# Sheet1.net
KiCad netlist of a schematic drawn in Altium Designer
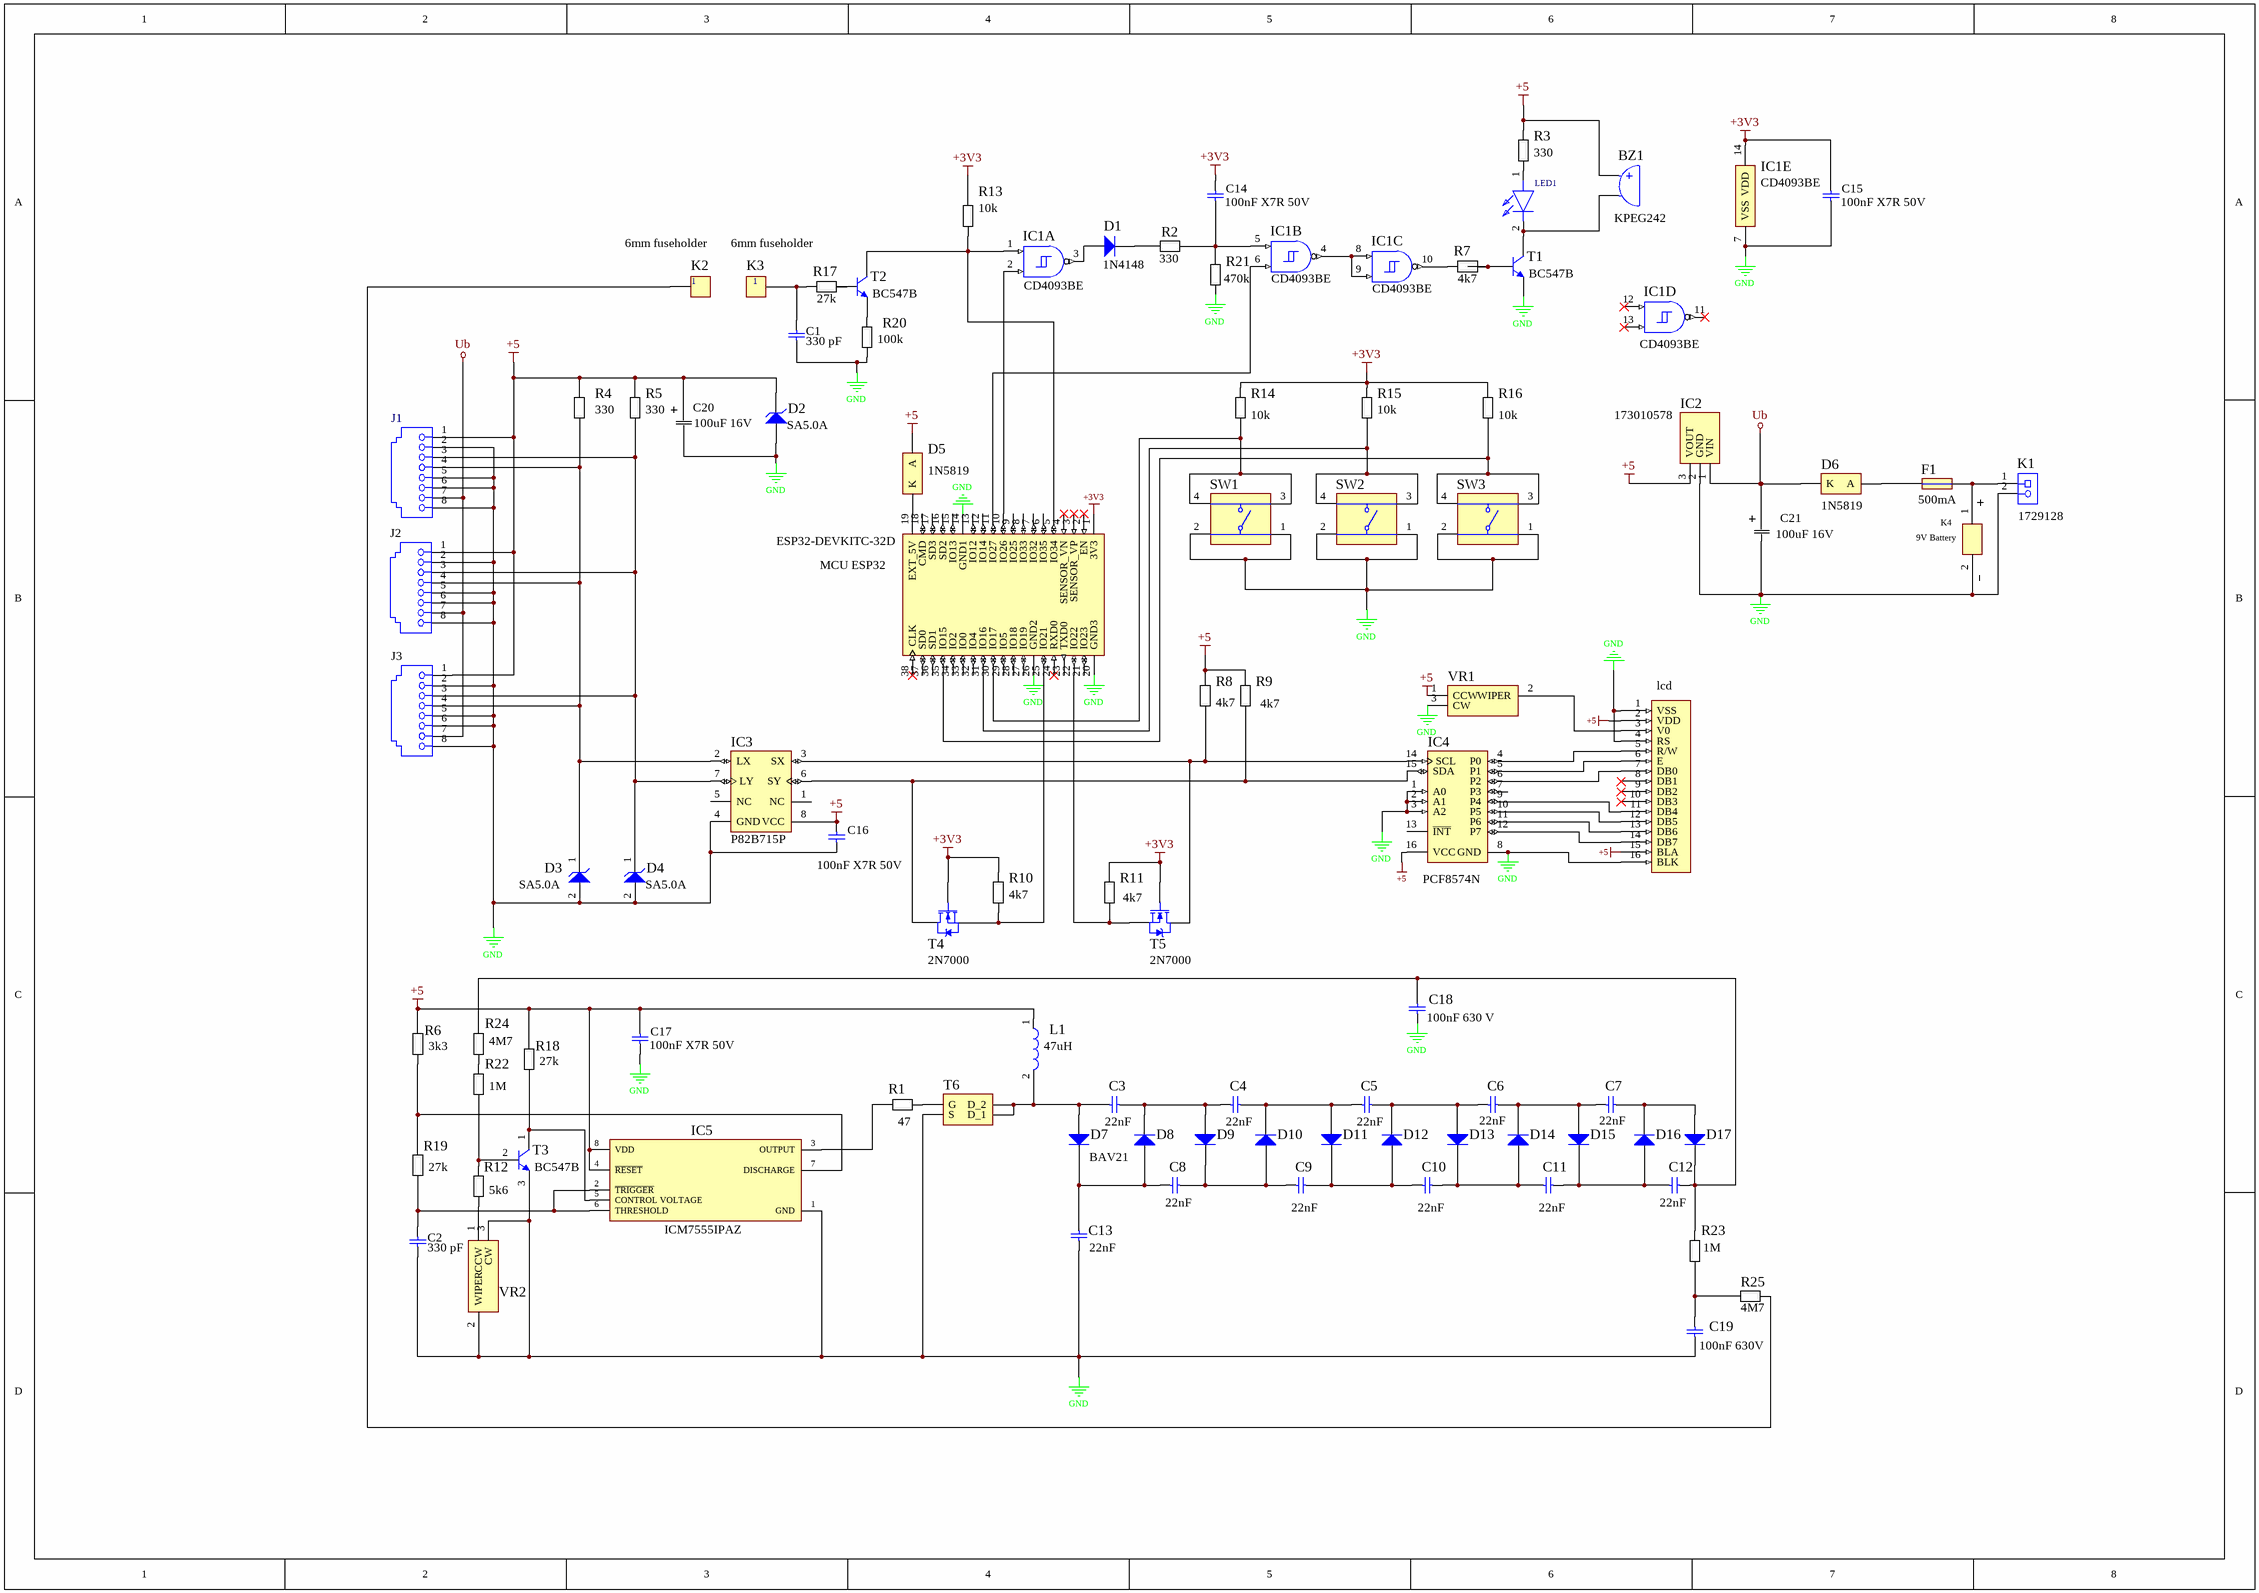
[diagram p0: Sheet1.SchDoc]

(export (version "E")
  (design (tool "Eeschema 10.0.6"))
  (components
    (comp (ref "BZ1")
      (value "KPEG242")
      (footprint "KINGS-KPEG242-2")
      (description "Piezo Indicator, 4100 Hz, 3 to 16 V, -20 to 70 degC, 2-Pin THD, RoHS")
      (fields (field (name "PARTNUMBER") "KPE-242") (field (name "MANUFACTURER") "KingstateElectronicsCorp."))
      (libsource (lib "Altium Content Vault") (part "KINGS-KPEG242-2"))
    )
    (comp (ref "C1")
      (value "330 pF")
      (footprint "CAPC2013X70X45NL10T25")
      (fields (field (name "MANUFACTURER") "Murata") (field (name "PART NUMBER") "GRM2165C1H332JA01D"))
      (libsource (lib "Altium Content Vault") (part "CAP"))
    )
    (comp (ref "C2")
      (value "330 pF")
      (footprint "CAPC2013X70X45NL10T25")
      (fields (field (name "MANUFACTURER") "Murata") (field (name "PART NUMBER") "GRM2165C1H332JA01D"))
      (libsource (lib "Altium Content Vault") (part "CAP"))
    )
    (comp (ref "C3")
      (value "22nF")
      (footprint "VISH-BFC233820104-2_V")
      (fields (field (name "PARTNUMBER") "BFC233820104") (field (name "MANUFACTURER") "Vishay Semiconductor"))
      (libsource (lib "Altium Content Vault") (part "VISH-CAP-NP-2"))
    )
    (comp (ref "C4")
      (value "22nF")
      (footprint "VISH-BFC233820104-2_V")
      (fields (field (name "PARTNUMBER") "BFC233820104") (field (name "MANUFACTURER") "Vishay Semiconductor"))
      (libsource (lib "Altium Content Vault") (part "VISH-CAP-NP-2"))
    )
    (comp (ref "C5")
      (value "22nF")
      (footprint "VISH-BFC233820104-2_V")
      (fields (field (name "PARTNUMBER") "BFC233820104") (field (name "MANUFACTURER") "Vishay Semiconductor"))
      (libsource (lib "Altium Content Vault") (part "VISH-CAP-NP-2"))
    )
    (comp (ref "C6")
      (value "22nF")
      (footprint "VISH-BFC233820104-2_V")
      (fields (field (name "PARTNUMBER") "BFC233820104") (field (name "MANUFACTURER") "Vishay Semiconductor"))
      (libsource (lib "Altium Content Vault") (part "VISH-CAP-NP-2"))
    )
    (comp (ref "C7")
      (value "22nF")
      (footprint "VISH-BFC233820104-2_V")
      (fields (field (name "PARTNUMBER") "BFC233820104") (field (name "MANUFACTURER") "Vishay Semiconductor"))
      (libsource (lib "Altium Content Vault") (part "VISH-CAP-NP-2"))
    )
    (comp (ref "C8")
      (value "22nF")
      (footprint "VISH-BFC233820104-2_V")
      (fields (field (name "PARTNUMBER") "BFC233820104") (field (name "MANUFACTURER") "Vishay Semiconductor"))
      (libsource (lib "Altium Content Vault") (part "VISH-CAP-NP-2"))
    )
    (comp (ref "C9")
      (value "22nF")
      (footprint "VISH-BFC233820104-2_V")
      (fields (field (name "PARTNUMBER") "BFC233820104") (field (name "MANUFACTURER") "Vishay Semiconductor"))
      (libsource (lib "Altium Content Vault") (part "VISH-CAP-NP-2"))
    )
    (comp (ref "C10")
      (value "22nF")
      (footprint "VISH-BFC233820104-2_V")
      (fields (field (name "PARTNUMBER") "BFC233820104") (field (name "MANUFACTURER") "Vishay Semiconductor"))
      (libsource (lib "Altium Content Vault") (part "VISH-CAP-NP-2"))
    )
    (comp (ref "C11")
      (value "22nF")
      (footprint "VISH-BFC233820104-2_V")
      (fields (field (name "PARTNUMBER") "BFC233820104") (field (name "MANUFACTURER") "Vishay Semiconductor"))
      (libsource (lib "Altium Content Vault") (part "VISH-CAP-NP-2"))
    )
    (comp (ref "C12")
      (value "22nF")
      (footprint "VISH-BFC233820104-2_V")
      (fields (field (name "PARTNUMBER") "BFC233820104") (field (name "MANUFACTURER") "Vishay Semiconductor"))
      (libsource (lib "Altium Content Vault") (part "VISH-CAP-NP-2"))
    )
    (comp (ref "C13")
      (value "22nF")
      (footprint "VISH-BFC233820104-2_V")
      (fields (field (name "PARTNUMBER") "BFC233820104") (field (name "MANUFACTURER") "Vishay Semiconductor"))
      (libsource (lib "Altium Content Vault") (part "VISH-CAP-NP-2"))
    )
    (comp (ref "C14")
      (value "100nF X7R 50V")
      (footprint "CAPC2013X70X45NL10T25")
      (fields (field (name "MANUFACTURER") "Murata") (field (name "PART NUMBER") "GRM2165C1H332JA01D"))
      (libsource (lib "Altium Content Vault") (part "CAP"))
    )
    (comp (ref "C15")
      (value "100nF X7R 50V")
      (footprint "CAPC2013X70X45NL10T25")
      (fields (field (name "MANUFACTURER") "Murata") (field (name "PART NUMBER") "GRM2165C1H332JA01D"))
      (libsource (lib "Altium Content Vault") (part "CAP"))
    )
    (comp (ref "C16")
      (value "100nF X7R 50V")
      (footprint "CAPC2013X70X45NL10T25")
      (fields (field (name "MANUFACTURER") "Murata") (field (name "PART NUMBER") "GRM2165C1H332JA01D"))
      (libsource (lib "Altium Content Vault") (part "CAP"))
    )
    (comp (ref "C17")
      (value "100nF X7R 50V")
      (footprint "CAPC2013X70X45NL10T25")
      (fields (field (name "MANUFACTURER") "Murata") (field (name "PART NUMBER") "GRM2165C1H332JA01D"))
      (libsource (lib "Altium Content Vault") (part "CAP"))
    )
    (comp (ref "C18")
      (value "100nF 630 V")
      (footprint "CAPC1812(4532)125_M")
      (description "CAP 470nF 50V ±10% 1812 (4532 Metric) Thickness 1.25mm SMD")
      (fields (field (name "TOLERANCE") "Â±10%"))
      (libsource (lib "Altium Content Vault") (part "CAP"))
    )
    (comp (ref "C19")
      (value "100nF 630V")
      (footprint "CAPC1812(4532)125_M")
      (description "CAP 470nF 50V ±10% 1812 (4532 Metric) Thickness 1.25mm SMD")
      (fields (field (name "TOLERANCE") "Â±10%"))
      (libsource (lib "Altium Content Vault") (part "CAP"))
    )
    (comp (ref "C20")
      (value "100uF 16V")
      (footprint "100uf 16V elco")
      (libsource (lib "Schlib2") (part "Component_1"))
    )
    (comp (ref "C21")
      (value "100uF 16V")
      (footprint "100uf 16V elco")
      (libsource (lib "Schlib2") (part "Component_1"))
    )
    (comp (ref "D1")
      (value "1N4148")
      (footprint "NXP-SOD27-2_V")
      (description "High-speed Diode, 100 V, 450 mA, 2-Pin SOD27, RoHS")
      (fields (field (name "MANUFACTURER") "NXP Semiconductors"))
      (libsource (lib "Altium Content Vault") (part "NXP-A1K2-2"))
    )
    (comp (ref "D2")
      (value "SA5.0A")
      (footprint "ONSC-AXIAL_LEAD-2-59AA-01_P")
      (fields (field (name "MANUFACTURER") "On Semiconductor"))
      (libsource (lib "") (part "ONSC-K1A2-2_1"))
    )
    (comp (ref "D3")
      (value "SA5.0A")
      (footprint "ONSC-AXIAL_LEAD-2-59AA-01_P")
      (fields (field (name "MANUFACTURER") "On Semiconductor"))
      (libsource (lib "Altium Content Vault") (part "ONSC-K1A2-2"))
    )
    (comp (ref "D4")
      (value "SA5.0A")
      (footprint "ONSC-AXIAL_LEAD-2-59AA-01_P")
      (fields (field (name "MANUFACTURER") "On Semiconductor"))
      (libsource (lib "Altium Content Vault") (part "ONSC-K1A2-2"))
    )
    (comp (ref "D5")
      (value "1N5819")
      (footprint "ONSC-AXIAL_LEAD-2-59-10_P")
      (description "Rectifier, 2-Pin Axial_Lead, Pb-Free, Bulk Bag")
      (fields (field (name "MANUFACTURER") "On Semiconductor"))
      (libsource (lib "") (part "ONSC-D-K1A2-2_A_1"))
    )
    (comp (ref "D6")
      (value "1N5819")
      (footprint "ONSC-AXIAL_LEAD-2-59-10_P")
      (description "Rectifier, 2-Pin Axial_Lead, Pb-Free, Bulk Bag")
      (fields (field (name "MANUFACTURER") "On Semiconductor"))
      (libsource (lib "Altium Content Vault") (part "ONSC-D-K1A2-2_A"))
    )
    (comp (ref "D7")
      (value "BAV21")
      (footprint "MCSM-DO-35-2")
      (description "BAV21TR Diode 250V 0.2A DO35")
      (fields (field (name "PARTNUMBER") "1N4148-1") (field (name "MANUFACTURER") "Microsemi"))
      (libsource (lib "Altium Content Vault") (part "D-AK-2"))
    )
    (comp (ref "D8")
      (value "BAV21")
      (footprint "MCSM-DO-35-2")
      (description "BAV21TR Diode 250V 0.2A DO35")
      (fields (field (name "PARTNUMBER") "1N4148-1") (field (name "MANUFACTURER") "Microsemi"))
      (libsource (lib "Altium Content Vault") (part "D-AK-2"))
    )
    (comp (ref "D9")
      (value "BAV21")
      (footprint "MCSM-DO-35-2")
      (description "BAV21TR Diode 250V 0.2A DO35")
      (fields (field (name "PARTNUMBER") "1N4148-1") (field (name "MANUFACTURER") "Microsemi"))
      (libsource (lib "Altium Content Vault") (part "D-AK-2"))
    )
    (comp (ref "D10")
      (value "BAV21")
      (footprint "MCSM-DO-35-2")
      (description "BAV21TR Diode 250V 0.2A DO35")
      (fields (field (name "PARTNUMBER") "1N4148-1") (field (name "MANUFACTURER") "Microsemi"))
      (libsource (lib "Altium Content Vault") (part "D-AK-2"))
    )
    (comp (ref "D11")
      (value "BAV21")
      (footprint "MCSM-DO-35-2")
      (description "BAV21TR Diode 250V 0.2A DO35")
      (fields (field (name "PARTNUMBER") "1N4148-1") (field (name "MANUFACTURER") "Microsemi"))
      (libsource (lib "Altium Content Vault") (part "D-AK-2"))
    )
    (comp (ref "D12")
      (value "BAV21")
      (footprint "MCSM-DO-35-2")
      (description "BAV21TR Diode 250V 0.2A DO35")
      (fields (field (name "PARTNUMBER") "1N4148-1") (field (name "MANUFACTURER") "Microsemi"))
      (libsource (lib "Altium Content Vault") (part "D-AK-2"))
    )
    (comp (ref "D13")
      (value "BAV21")
      (footprint "MCSM-DO-35-2")
      (description "BAV21TR Diode 250V 0.2A DO35")
      (fields (field (name "PARTNUMBER") "1N4148-1") (field (name "MANUFACTURER") "Microsemi"))
      (libsource (lib "Altium Content Vault") (part "D-AK-2"))
    )
    (comp (ref "D14")
      (value "BAV21")
      (footprint "MCSM-DO-35-2")
      (description "BAV21TR Diode 250V 0.2A DO35")
      (fields (field (name "PARTNUMBER") "1N4148-1") (field (name "MANUFACTURER") "Microsemi"))
      (libsource (lib "Altium Content Vault") (part "D-AK-2"))
    )
    (comp (ref "D15")
      (value "BAV21")
      (footprint "MCSM-DO-35-2")
      (description "BAV21TR Diode 250V 0.2A DO35")
      (fields (field (name "PARTNUMBER") "1N4148-1") (field (name "MANUFACTURER") "Microsemi"))
      (libsource (lib "Altium Content Vault") (part "D-AK-2"))
    )
    (comp (ref "D16")
      (value "BAV21")
      (footprint "MCSM-DO-35-2")
      (description "BAV21TR Diode 250V 0.2A DO35")
      (fields (field (name "PARTNUMBER") "1N4148-1") (field (name "MANUFACTURER") "Microsemi"))
      (libsource (lib "Altium Content Vault") (part "D-AK-2"))
    )
    (comp (ref "D17")
      (value "BAV21")
      (footprint "MCSM-DO-35-2")
      (description "BAV21TR Diode 250V 0.2A DO35")
      (fields (field (name "PARTNUMBER") "1N4148-1") (field (name "MANUFACTURER") "Microsemi"))
      (libsource (lib "Altium Content Vault") (part "D-AK-2"))
    )
    (comp (ref "F1")
      (value "500mA")
      (footprint "39211000000")
      (description "Fuse")
      (fields
        (field (name "MANUFACTURER_PART_NUMBER") "39211000000")
        (field (name "MOUSER PART NUMBER") "576-3921100000")
      )
      (libsource (lib "SamacSys") (part "39211000000"))
    )
    (comp (ref "IC1")
      (value "CD4093BE")
      (footprint "N0014A")
      (description "CMOS Quad 2-Input NAND Schmitt Triggers, N0014A, TUBE")
      (fields
        (field (name "MANUFACTURER") "Texas Instruments")
        (field (name "GENERIC PART NUMBER") "CD4093B")
      )
      (libsource (lib "Altium Content Vault") (part "TI-NAND-4-2IN-14_A-SCHMITT"))
    )
    (comp (ref "IC2")
      (value "173010578")
      (footprint "173010578")
      (description "Undefined or Miscellaneous")
      (fields (field (name "MOUSER2 PART NUMBER") "710-173010578"))
      (libsource (lib "SamacSys") (part "173010578"))
    )
    (comp (ref "IC3")
      (value "P82B715P")
      (footprint "P0008A")
      (description "I2C Bus Extender, 2 Channel Width, 3.0 to 12.0 V, -40 to 85 degC, 8-pin PDIP (P), Pb-Free (RoHS)")
      (fields (field (name "MANUFACTURER") "Texas Instruments"))
      (libsource (lib "Altium Content Vault") (part "TI-P82B715-PDIP_P-8"))
    )
    (comp (ref "IC4")
      (value "PCF8574N")
      (footprint "N0016A")
      (description "Remote 8-Bit I/O Expander for I2C-Bus, 2.5 to 6 V, -40 to 85 degC, 16-pin PDIP (N), Pb-Free (RoHS)")
      (fields (field (name "MANUFACTURER") "Texas Instruments"))
      (libsource (lib "Altium Content Vault") (part "TI-PCF8574-PDIP_N-16"))
    )
    (comp (ref "IC5")
      (value "ICM7555IPAZ")
      (footprint "Intersil_ICM7555IPAZ_0")
      (libsource (lib "IC_Intersil_ICM7555IPAZ_eec") (part "ICM7555IPAZ"))
    )
    (comp (ref "J1")
      (value "615008138021")
      (footprint "615008138021")
      (description "Modular Jack WR-MJ, Plastic, Vertical Entry, THT, 8P8C")
      (fields (field (name "MANUFACTURER") "Wurth Elektronik") (field (name "PUBLISHER") "WurthElektronik"))
      (libsource (lib "Altium Content Vault") (part "WE-CN-1P-F-J8"))
    )
    (comp (ref "J2")
      (value "615008138021")
      (footprint "615008138021")
      (description "Modular Jack WR-MJ, Plastic, Vertical Entry, THT, 8P8C")
      (fields (field (name "MANUFACTURER") "Wurth Elektronik") (field (name "PUBLISHER") "WurthElektronik"))
      (libsource (lib "Altium Content Vault") (part "WE-CN-1P-F-J8"))
    )
    (comp (ref "J3")
      (value "615008138021")
      (footprint "615008138021")
      (description "Modular Jack WR-MJ, Plastic, Vertical Entry, THT, 8P8C")
      (fields (field (name "MANUFACTURER") "Wurth Elektronik") (field (name "PUBLISHER") "WurthElektronik"))
      (libsource (lib "Altium Content Vault") (part "WE-CN-1P-F-J8"))
    )
    (comp (ref "K1")
      (value "1729128")
      (footprint "PHOE-1729128-2_V")
      (description "PCB Terminal Block, 13.5 A, 400 V, 2-Pin THD, RoHS, Bulk")
      (fields (field (name "MANUFACTURER") "Phoenix Contact"))
      (libsource (lib "Altium Content Vault") (part "CN-2P-F-R2"))
    )
    (comp (ref "K2")
      (value "6mm fuseholder")
      (footprint "FP-102-MFG")
      (description "FUSE CLIP CARTRIDGE 250V 15A PCB")
      (fields
        (field (name "MANUFACTURER") "Littelfuse Inc")
        (field (name "OCTOPART") "https://octopart.com/01020071z-littelfuse-18837869")
      )
      (libsource (lib "") (part "600373309f0643ccfefc365bd0e8f7b_1"))
    )
    (comp (ref "K3")
      (value "6mm fuseholder")
      (footprint "FP-102-MFG")
      (description "FUSE CLIP CARTRIDGE 250V 15A PCB")
      (fields
        (field (name "MANUFACTURER") "Littelfuse Inc")
        (field (name "OCTOPART") "https://octopart.com/01020071z-littelfuse-18837869")
      )
      (libsource (lib "Altium Content Vault") (part "600373309f0643ccfefc365bd0e8f7b"))
    )
    (comp (ref "K4")
      (value "9V Battery")
      (footprint "PCBComponent_1")
      (libsource (lib "Schlib3") (part "Component_1"))
    )
    (comp (ref "L1")
      (value "47uH")
      (footprint "WE-TI-LS")
      (description "Radial Leaded Wire Wound Inductor WE-TI, L = 100 µH")
      (libsource (lib "Altium Content Vault") (part "PAS-IND-INDUCTOR-2"))
    )
    (comp (ref "lcd") (value "~") (footprint "PCBComponent_1") (libsource (lib "1602a") (part "Component_1")))
    (comp (ref "LED1")
      (value "151033GS03000")
      (footprint "SamacSys:151033GS03000")
      (description "LED")
      (fields (field (name "MOUSER PART NUMBER") "710-151033GS03000"))
      (libsource (lib "SamacSys") (part "151033GS03000"))
    )
    (comp (ref "MCU ESP32")
      (value "ESP32-DEVKITC-32D")
      (footprint "MODULE_ESP32-DEVKITC-32D")
      (description "EVAL BOARD FOR ESP-WROOM-32")
      (fields (field (name "MF") "Espressif Systems"))
      (libsource (lib "ESP32-DEVKITC-32D") (part "ESP32-DEVKITC-32D"))
    )
    (comp (ref "R1")
      (value "47")
      (footprint "FP-RC1206-IPC_C")
      (libsource (lib "") (part "1206 weerstand_2"))
    )
    (comp (ref "R2")
      (value "330")
      (footprint "FP-RC1206-IPC_C")
      (libsource (lib "") (part "1206 weerstand_3"))
    )
    (comp (ref "R3")
      (value "330")
      (footprint "FP-RC1206-IPC_C")
      (libsource (lib "") (part "1206 weerstand_1"))
    )
    (comp (ref "R4")
      (value "330")
      (footprint "FP-RC1206-IPC_C")
      (libsource (lib "Schlib1") (part "1206 weerstand"))
    )
    (comp (ref "R5")
      (value "330")
      (footprint "FP-RC1206-IPC_C")
      (libsource (lib "Schlib1") (part "1206 weerstand"))
    )
    (comp (ref "R6")
      (value "3k3")
      (footprint "FP-RC1206-IPC_C")
      (libsource (lib "Schlib1") (part "1206 weerstand"))
    )
    (comp (ref "R7")
      (value "4k7")
      (footprint "FP-RC1206-IPC_C")
      (libsource (lib "") (part "1206 weerstand_2"))
    )
    (comp (ref "R8")
      (value "4k7")
      (footprint "FP-RC1206-IPC_C")
      (libsource (lib "Schlib1") (part "1206 weerstand"))
    )
    (comp (ref "R9")
      (value "4k7")
      (footprint "FP-RC1206-IPC_C")
      (libsource (lib "Schlib1") (part "1206 weerstand"))
    )
    (comp (ref "R10")
      (value "4k7")
      (footprint "FP-RC1206-IPC_C")
      (libsource (lib "Schlib1") (part "1206 weerstand"))
    )
    (comp (ref "R11")
      (value "4k7")
      (footprint "FP-RC1206-IPC_C")
      (libsource (lib "") (part "1206 weerstand_3"))
    )
    (comp (ref "R12")
      (value "5k6")
      (footprint "FP-RC1206-IPC_C")
      (libsource (lib "Schlib1") (part "1206 weerstand"))
    )
    (comp (ref "R13")
      (value "10k")
      (footprint "FP-RC1206-IPC_C")
      (libsource (lib "") (part "1206 weerstand_1"))
    )
    (comp (ref "R14")
      (value "10k")
      (footprint "FP-RC1206-IPC_C")
      (libsource (lib "Schlib1") (part "1206 weerstand"))
    )
    (comp (ref "R15")
      (value "10k")
      (footprint "FP-RC1206-IPC_C")
      (libsource (lib "Schlib1") (part "1206 weerstand"))
    )
    (comp (ref "R16")
      (value "10k")
      (footprint "FP-RC1206-IPC_C")
      (libsource (lib "Schlib1") (part "1206 weerstand"))
    )
    (comp (ref "R17")
      (value "27k")
      (footprint "FP-RC1206-IPC_C")
      (libsource (lib "") (part "1206 weerstand_2"))
    )
    (comp (ref "R18")
      (value "27k")
      (footprint "FP-RC1206-IPC_C")
      (libsource (lib "Schlib1") (part "1206 weerstand"))
    )
    (comp (ref "R19")
      (value "27k")
      (footprint "FP-RC1206-IPC_C")
      (libsource (lib "Schlib1") (part "1206 weerstand"))
    )
    (comp (ref "R20")
      (value "100k")
      (footprint "FP-RC1206-IPC_C")
      (libsource (lib "") (part "1206 weerstand_1"))
    )
    (comp (ref "R21")
      (value "470k")
      (footprint "FP-RC1206-IPC_C")
      (libsource (lib "Schlib1") (part "1206 weerstand"))
    )
    (comp (ref "R22")
      (value "1M")
      (footprint "RES_VR25")
      (description "No Description Available")
      (fields
        (field (name "MANUFACTURER_PART_NUMBER") "VR25000001004JA100")
        (field (name "COPYRIGHT") "Copyright (C) 2018 Accelerated Designs. All rights reserved")
      )
      (libsource (lib "2021-03-05_17-49-49") (part "VR25000001004JA100"))
    )
    (comp (ref "R23")
      (value "1M")
      (footprint "RES_VR25")
      (description "No Description Available")
      (fields
        (field (name "MANUFACTURER_PART_NUMBER") "VR25000001004JA100")
        (field (name "COPYRIGHT") "Copyright (C) 2018 Accelerated Designs. All rights reserved")
      )
      (libsource (lib "2021-03-05_17-49-49") (part "VR25000001004JA100"))
    )
    (comp (ref "R24")
      (value "4M7")
      (footprint "RES_VR25")
      (description "No Description Available")
      (fields
        (field (name "MANUFACTURER_PART_NUMBER") "VR25000001004JA100")
        (field (name "COPYRIGHT") "Copyright (C) 2018 Accelerated Designs. All rights reserved")
      )
      (libsource (lib "2021-03-05_17-49-49") (part "VR25000001004JA100"))
    )
    (comp (ref "R25")
      (value "4M7")
      (footprint "RES_VR25")
      (description "No Description Available")
      (fields
        (field (name "MANUFACTURER_PART_NUMBER") "VR25000001004JA100")
        (field (name "COPYRIGHT") "Copyright (C) 2018 Accelerated Designs. All rights reserved")
      )
      (libsource (lib "") (part "VR25000001004JA100_1"))
    )
    (comp (ref "SW1")
      (value "tactile switch 10mm")
      (footprint "TECO-1825910-6_V")
      (description "Tact Switch, SPST-NO, 0.05 A, -35 to 85 degC, 4-Pin THD, RoHS, Bulk")
      (fields (field (name "PART NO") "1825910-6") (field (name "MANUFACTURER") "TE Connectivity"))
      (libsource (lib "Altium Content Vault") (part "SW-SPST-4_A"))
    )
    (comp (ref "SW2")
      (value "tactile switch 10mm")
      (footprint "TECO-1825910-6_V")
      (description "Tact Switch, SPST-NO, 0.05 A, -35 to 85 degC, 4-Pin THD, RoHS, Bulk")
      (fields (field (name "PART NO") "1825910-6") (field (name "MANUFACTURER") "TE Connectivity"))
      (libsource (lib "Altium Content Vault") (part "SW-SPST-4_A"))
    )
    (comp (ref "SW3")
      (value "tactile switch 10mm")
      (footprint "TECO-1825910-6_V")
      (description "Tact Switch, SPST-NO, 0.05 A, -35 to 85 degC, 4-Pin THD, RoHS, Bulk")
      (fields (field (name "PART NO") "1825910-6") (field (name "MANUFACTURER") "TE Connectivity"))
      (libsource (lib "Altium Content Vault") (part "SW-SPST-4_A"))
    )
    (comp (ref "T1")
      (value "BC547B")
      (footprint "ONSC-TO-92-3-29-11")
      (description "Amplifier Transistor, NPN Silicon, 3-Pin TO-92, Bulk Box")
      (fields (field (name "MANUFACTURER") "On Semiconductor"))
      (libsource (lib "") (part "ONSC-NPN-C1B2E3-3_1"))
    )
    (comp (ref "T2")
      (value "BC547B")
      (footprint "ONSC-TO-92-3-29-11")
      (description "Amplifier Transistor, NPN Silicon, 3-Pin TO-92, Bulk Box")
      (fields (field (name "MANUFACTURER") "On Semiconductor"))
      (libsource (lib "") (part "ONSC-NPN-C1B2E3-3_1"))
    )
    (comp (ref "T3")
      (value "BC547B")
      (footprint "ONSC-TO-92-3-29-11")
      (description "Amplifier Transistor, NPN Silicon, 3-Pin TO-92, Bulk Box")
      (fields (field (name "MANUFACTURER") "On Semiconductor"))
      (libsource (lib "Altium Content Vault") (part "ONSC-NPN-C1B2E3-3"))
    )
    (comp (ref "T4")
      (value "2N7000")
      (footprint "ONSC-TO-92-3-29-11")
      (description "Small Signal MOSFET, 200 mA, 60 V, N-Channel, 3-Pin TO-92, Bulk Box")
      (fields (field (name "MANUFACTURER") "On Semiconductor"))
      (libsource (lib "Altium Content Vault") (part "ONSC-NMOS-S1G2D3-3"))
    )
    (comp (ref "T5")
      (value "2N7000")
      (footprint "ONSC-TO-92-3-29-11")
      (description "Small Signal MOSFET, 200 mA, 60 V, N-Channel, 3-Pin TO-92, Bulk Box")
      (fields (field (name "MANUFACTURER") "On Semiconductor"))
      (libsource (lib "Altium Content Vault") (part "ONSC-NMOS-S1G2D3-3"))
    )
    (comp (ref "T6")
      (value "~")
      (footprint "SamacSys:DIP920W60P254L490H337Q4N")
      (description "MOSFET (N-Channel)")
      (fields
        (field (name "MANUFACTURER_PART_NUMBER") "IRLD110PBF")
        (field (name "MOUSER PART NUMBER") "844-IRLD110PBF")
      )
      (libsource (lib "SamacSys") (part "IRLD110PBF"))
    )
    (comp (ref "VR1")
      (value "~")
      (footprint "RM065102")
      (description "Variable Resistor")
      (fields (field (name "MANUFACTURER_PART_NUMBER") "RM-065-102"))
      (libsource (lib "SamacSys") (part "RM-065-102"))
    )
    (comp (ref "VR2")
      (value "~")
      (footprint "RM065102")
      (description "Variable Resistor")
      (fields (field (name "MANUFACTURER_PART_NUMBER") "RM-065-102"))
      (libsource (lib "") (part "RM-065-102_1"))
    )
  )
  (nets
    (net (code "1") (name "+3V3") (class "Default")
      (node (ref "C14") (pin "2") (pinfunction "2_2") (pintype "passive"))
      (node (ref "C15") (pin "2") (pinfunction "2_2") (pintype "passive"))
      (node (ref "IC1") (pin "14") (pinfunction "VDD_14") (pintype "power_in"))
      (node (ref "MCU ESP32") (pin "1") (pinfunction "3V3_1") (pintype "power_in"))
      (node (ref "R10") (pin "2") (pintype "passive"))
      (node (ref "R11") (pin "2") (pintype "passive"))
      (node (ref "R13") (pin "1") (pintype "passive"))
      (node (ref "R14") (pin "2") (pintype "passive"))
      (node (ref "R15") (pin "2") (pintype "passive"))
      (node (ref "R16") (pin "2") (pintype "passive"))
      (node (ref "T4") (pin "2") (pinfunction "G_2") (pintype "passive"))
      (node (ref "T5") (pin "2") (pinfunction "G_2") (pintype "passive"))
    )
    (net (code "2") (name "+5") (class "Default")
      (node (ref "BZ1") (pin "1") (pinfunction "1_1") (pintype "passive"))
      (node (ref "C16") (pin "2") (pinfunction "2_2") (pintype "passive"))
      (node (ref "C17") (pin "2") (pinfunction "2_2") (pintype "passive"))
      (node (ref "C20") (pin "2") (pintype "passive"))
      (node (ref "D2") (pin "1") (pinfunction "K_1") (pintype "passive"))
      (node (ref "D5") (pin "2") (pinfunction "A_2") (pintype "passive"))
      (node (ref "IC2") (pin "3") (pinfunction "VOUT_3") (pintype "passive"))
      (node (ref "IC3") (pin "8") (pinfunction "VCC_8") (pintype "power_in"))
      (node (ref "IC4") (pin "16") (pinfunction "VCC_16") (pintype "power_in"))
      (node (ref "IC5") (pin "4") (pinfunction "~{RESET}_4") (pintype "passive"))
      (node (ref "IC5") (pin "8") (pinfunction "VDD_8") (pintype "passive"))
      (node (ref "J1") (pin "1") (pinfunction "1_1") (pintype "passive"))
      (node (ref "J2") (pin "1") (pinfunction "1_1") (pintype "passive"))
      (node (ref "J3") (pin "1") (pinfunction "1_1") (pintype "passive"))
      (node (ref "L1") (pin "1") (pinfunction "1_1") (pintype "passive"))
      (node (ref "R18") (pin "2") (pintype "passive"))
      (node (ref "R3") (pin "1") (pintype "passive"))
      (node (ref "R4") (pin "2") (pintype "passive"))
      (node (ref "R5") (pin "2") (pintype "passive"))
      (node (ref "R6") (pin "2") (pintype "passive"))
      (node (ref "R8") (pin "2") (pintype "passive"))
      (node (ref "R9") (pin "2") (pintype "passive"))
      (node (ref "VR1") (pin "1") (pinfunction "CCW_1") (pintype "passive"))
      (node (ref "lcd") (pin "15") (pinfunction "BLA_15") (pintype "input"))
      (node (ref "lcd") (pin "2") (pinfunction "VDD_2") (pintype "input"))
    )
    (net (code "3") (name "GND") (class "Default")
      (node (ref "C1") (pin "1") (pinfunction "1_1") (pintype "passive"))
      (node (ref "C13") (pin "1") (pinfunction "1_1") (pintype "passive"))
      (node (ref "C15") (pin "1") (pinfunction "1_1") (pintype "passive"))
      (node (ref "C16") (pin "1") (pinfunction "1_1") (pintype "passive"))
      (node (ref "C17") (pin "1") (pinfunction "1_1") (pintype "passive"))
      (node (ref "C18") (pin "1") (pinfunction "1_1") (pintype "passive"))
      (node (ref "C19") (pin "1") (pinfunction "1_1") (pintype "passive"))
      (node (ref "C2") (pin "1") (pinfunction "1_1") (pintype "passive"))
      (node (ref "C20") (pin "1") (pintype "passive"))
      (node (ref "C21") (pin "1") (pintype "passive"))
      (node (ref "D2") (pin "2") (pinfunction "A_2") (pintype "passive"))
      (node (ref "D3") (pin "2") (pinfunction "A_2") (pintype "passive"))
      (node (ref "D4") (pin "2") (pinfunction "A_2") (pintype "passive"))
      (node (ref "IC1") (pin "7") (pinfunction "VSS_7") (pintype "power_in"))
      (node (ref "IC2") (pin "2") (pinfunction "GND_2") (pintype "passive"))
      (node (ref "IC3") (pin "4") (pinfunction "GND_4") (pintype "power_in"))
      (node (ref "IC4") (pin "1") (pinfunction "A0_1") (pintype "input"))
      (node (ref "IC4") (pin "2") (pinfunction "A1_2") (pintype "input"))
      (node (ref "IC4") (pin "3") (pinfunction "A2_3") (pintype "input"))
      (node (ref "IC4") (pin "8") (pinfunction "GND_8") (pintype "power_in"))
      (node (ref "IC5") (pin "1") (pinfunction "GND_1") (pintype "passive"))
      (node (ref "J1") (pin "2") (pinfunction "2_2") (pintype "passive"))
      (node (ref "J1") (pin "5") (pinfunction "5_5") (pintype "passive"))
      (node (ref "J1") (pin "6") (pinfunction "6_6") (pintype "passive"))
      (node (ref "J1") (pin "8") (pinfunction "8_8") (pintype "passive"))
      (node (ref "J2") (pin "2") (pinfunction "2_2") (pintype "passive"))
      (node (ref "J2") (pin "5") (pinfunction "5_5") (pintype "passive"))
      (node (ref "J2") (pin "6") (pinfunction "6_6") (pintype "passive"))
      (node (ref "J2") (pin "8") (pinfunction "8_8") (pintype "passive"))
      (node (ref "J3") (pin "2") (pinfunction "2_2") (pintype "passive"))
      (node (ref "J3") (pin "5") (pinfunction "5_5") (pintype "passive"))
      (node (ref "J3") (pin "6") (pinfunction "6_6") (pintype "passive"))
      (node (ref "J3") (pin "8") (pinfunction "8_8") (pintype "passive"))
      (node (ref "K1") (pin "2") (pinfunction "2_2") (pintype "passive"))
      (node (ref "K4") (pin "2") (pintype "power_in"))
      (node (ref "MCU ESP32") (pin "14") (pinfunction "GND1_14") (pintype "power_in"))
      (node (ref "MCU ESP32") (pin "20") (pinfunction "GND3_20") (pintype "power_in"))
      (node (ref "MCU ESP32") (pin "26") (pinfunction "GND2_26") (pintype "power_in"))
      (node (ref "R20") (pin "2") (pintype "passive"))
      (node (ref "R21") (pin "1") (pintype "passive"))
      (node (ref "SW1") (pin "1") (pinfunction "1_1") (pintype "passive"))
      (node (ref "SW1") (pin "2") (pinfunction "2_2") (pintype "passive"))
      (node (ref "SW2") (pin "1") (pinfunction "1_1") (pintype "passive"))
      (node (ref "SW2") (pin "2") (pinfunction "2_2") (pintype "passive"))
      (node (ref "SW3") (pin "1") (pinfunction "1_1") (pintype "passive"))
      (node (ref "SW3") (pin "2") (pinfunction "2_2") (pintype "passive"))
      (node (ref "T1") (pin "3") (pinfunction "E_3") (pintype "passive"))
      (node (ref "T3") (pin "3") (pinfunction "E_3") (pintype "passive"))
      (node (ref "T6") (pin "2") (pinfunction "S_2") (pintype "passive"))
      (node (ref "VR1") (pin "3") (pinfunction "CW_3") (pintype "passive"))
      (node (ref "VR2") (pin "2") (pinfunction "WIPER_2") (pintype "passive"))
      (node (ref "VR2") (pin "3") (pinfunction "CW_3") (pintype "passive"))
      (node (ref "lcd") (pin "1") (pinfunction "VSS_1") (pintype "input"))
      (node (ref "lcd") (pin "16") (pinfunction "BLK_16") (pintype "input"))
      (node (ref "lcd") (pin "4") (pinfunction "RS_4") (pintype "input"))
    )
    (net (code "4") (name "Net-(C1-Pad2)") (class "Default")
      (node (ref "C1") (pin "2") (pinfunction "2_2") (pintype "passive"))
      (node (ref "K3") (pin "1") (pinfunction "1_1") (pintype "passive"))
      (node (ref "R17") (pin "2") (pintype "passive"))
    )
    (net (code "5") (name "Net-(C19-Pad2)") (class "Default")
      (node (ref "C19") (pin "2") (pinfunction "2_2") (pintype "passive"))
      (node (ref "R23") (pin "1") (pintype "passive"))
      (node (ref "R25") (pin "1") (pintype "passive"))
    )
    (net (code "6") (name "Net-(D1-A)") (class "Default")
      (node (ref "D1") (pin "1") (pinfunction "A_1") (pintype "passive"))
      (node (ref "IC1") (pin "3") (pinfunction "J_3") (pintype "output"))
    )
    (net (code "7") (name "Net-(D1-K)") (class "Default")
      (node (ref "D1") (pin "2") (pinfunction "K_2") (pintype "passive"))
      (node (ref "R2") (pin "1") (pintype "passive"))
    )
    (net (code "8") (name "Net-(D3-K)") (class "Default")
      (node (ref "D3") (pin "1") (pinfunction "K_1") (pintype "passive"))
      (node (ref "IC3") (pin "2") (pinfunction "LX_2") (pintype "bidirectional"))
      (node (ref "J1") (pin "4") (pinfunction "4_4") (pintype "passive"))
      (node (ref "J2") (pin "4") (pinfunction "4_4") (pintype "passive"))
      (node (ref "J3") (pin "4") (pinfunction "4_4") (pintype "passive"))
      (node (ref "R4") (pin "1") (pintype "passive"))
    )
    (net (code "9") (name "Net-(D4-K)") (class "Default")
      (node (ref "D4") (pin "1") (pinfunction "K_1") (pintype "passive"))
      (node (ref "IC3") (pin "7") (pinfunction "LY_7") (pintype "bidirectional"))
      (node (ref "J1") (pin "3") (pinfunction "3_3") (pintype "passive"))
      (node (ref "J2") (pin "3") (pinfunction "3_3") (pintype "passive"))
      (node (ref "J3") (pin "3") (pinfunction "3_3") (pintype "passive"))
      (node (ref "R5") (pin "1") (pintype "passive"))
    )
    (net (code "10") (name "Net-(D5-K)") (class "Default")
      (node (ref "D5") (pin "1") (pinfunction "K_1") (pintype "passive"))
      (node (ref "MCU ESP32") (pin "19") (pinfunction "EXT_5V_19") (pintype "power_in"))
    )
    (net (code "11") (name "Net-(D6-A)") (class "Default")
      (node (ref "D6") (pin "2") (pinfunction "A_2") (pintype "passive"))
      (node (ref "F1") (pin "1") (pinfunction "1_1") (pintype "passive"))
    )
    (net (code "12") (name "Net-(D7-A)") (class "Default")
      (node (ref "C3") (pin "1") (pinfunction "1_1") (pintype "passive"))
      (node (ref "D7") (pin "1") (pinfunction "A_1") (pintype "passive"))
      (node (ref "L1") (pin "2") (pinfunction "2_2") (pintype "passive"))
      (node (ref "T6") (pin "3") (pinfunction "D_1_3") (pintype "passive"))
      (node (ref "T6") (pin "4") (pinfunction "D_2_4") (pintype "passive"))
    )
    (net (code "13") (name "Net-(D7-K)") (class "Default")
      (node (ref "C13") (pin "2") (pinfunction "2_2") (pintype "passive"))
      (node (ref "C8") (pin "1") (pinfunction "1_1") (pintype "passive"))
      (node (ref "D7") (pin "2") (pinfunction "K_2") (pintype "passive"))
      (node (ref "D8") (pin "1") (pinfunction "A_1") (pintype "passive"))
    )
    (net (code "14") (name "Net-(D8-K)") (class "Default")
      (node (ref "C3") (pin "2") (pinfunction "2_2") (pintype "passive"))
      (node (ref "C4") (pin "1") (pinfunction "1_1") (pintype "passive"))
      (node (ref "D8") (pin "2") (pinfunction "K_2") (pintype "passive"))
      (node (ref "D9") (pin "1") (pinfunction "A_1") (pintype "passive"))
    )
    (net (code "15") (name "Net-(D10-A)") (class "Default")
      (node (ref "C8") (pin "2") (pinfunction "2_2") (pintype "passive"))
      (node (ref "C9") (pin "1") (pinfunction "1_1") (pintype "passive"))
      (node (ref "D10") (pin "1") (pinfunction "A_1") (pintype "passive"))
      (node (ref "D9") (pin "2") (pinfunction "K_2") (pintype "passive"))
    )
    (net (code "16") (name "Net-(D10-K)") (class "Default")
      (node (ref "C4") (pin "2") (pinfunction "2_2") (pintype "passive"))
      (node (ref "C5") (pin "1") (pinfunction "1_1") (pintype "passive"))
      (node (ref "D10") (pin "2") (pinfunction "K_2") (pintype "passive"))
      (node (ref "D11") (pin "1") (pinfunction "A_1") (pintype "passive"))
    )
    (net (code "17") (name "Net-(D11-K)") (class "Default")
      (node (ref "C10") (pin "1") (pinfunction "1_1") (pintype "passive"))
      (node (ref "C9") (pin "2") (pinfunction "2_2") (pintype "passive"))
      (node (ref "D11") (pin "2") (pinfunction "K_2") (pintype "passive"))
      (node (ref "D12") (pin "1") (pinfunction "A_1") (pintype "passive"))
    )
    (net (code "18") (name "Net-(D12-K)") (class "Default")
      (node (ref "C5") (pin "2") (pinfunction "2_2") (pintype "passive"))
      (node (ref "C6") (pin "1") (pinfunction "1_1") (pintype "passive"))
      (node (ref "D12") (pin "2") (pinfunction "K_2") (pintype "passive"))
      (node (ref "D13") (pin "1") (pinfunction "A_1") (pintype "passive"))
    )
    (net (code "19") (name "Net-(D13-K)") (class "Default")
      (node (ref "C10") (pin "2") (pinfunction "2_2") (pintype "passive"))
      (node (ref "C11") (pin "1") (pinfunction "1_1") (pintype "passive"))
      (node (ref "D13") (pin "2") (pinfunction "K_2") (pintype "passive"))
      (node (ref "D14") (pin "1") (pinfunction "A_1") (pintype "passive"))
    )
    (net (code "20") (name "Net-(D14-K)") (class "Default")
      (node (ref "C6") (pin "2") (pinfunction "2_2") (pintype "passive"))
      (node (ref "C7") (pin "1") (pinfunction "1_1") (pintype "passive"))
      (node (ref "D14") (pin "2") (pinfunction "K_2") (pintype "passive"))
      (node (ref "D15") (pin "1") (pinfunction "A_1") (pintype "passive"))
    )
    (net (code "21") (name "Net-(D15-K)") (class "Default")
      (node (ref "C11") (pin "2") (pinfunction "2_2") (pintype "passive"))
      (node (ref "C12") (pin "1") (pinfunction "1_1") (pintype "passive"))
      (node (ref "D15") (pin "2") (pinfunction "K_2") (pintype "passive"))
      (node (ref "D16") (pin "1") (pinfunction "A_1") (pintype "passive"))
    )
    (net (code "22") (name "Net-(D16-K)") (class "Default")
      (node (ref "C7") (pin "2") (pinfunction "2_2") (pintype "passive"))
      (node (ref "D16") (pin "2") (pinfunction "K_2") (pintype "passive"))
      (node (ref "D17") (pin "1") (pinfunction "A_1") (pintype "passive"))
    )
    (net (code "23") (name "Net-(D17-K)") (class "Default")
      (node (ref "C12") (pin "2") (pinfunction "2_2") (pintype "passive"))
      (node (ref "C18") (pin "2") (pinfunction "2_2") (pintype "passive"))
      (node (ref "D17") (pin "2") (pinfunction "K_2") (pintype "passive"))
      (node (ref "R23") (pin "2") (pintype "passive"))
      (node (ref "R24") (pin "2") (pintype "passive"))
    )
    (net (code "24") (name "Net-(F1-Pad2)") (class "Default")
      (node (ref "F1") (pin "2") (pinfunction "2_2") (pintype "passive"))
      (node (ref "K1") (pin "1") (pinfunction "1_1") (pintype "passive"))
      (node (ref "K4") (pin "1") (pintype "power_in"))
    )
    (net (code "25") (name "Net-(IC1A-A)") (class "Default")
      (node (ref "IC1") (pin "1") (pinfunction "A_1") (pintype "input"))
      (node (ref "MCU ESP32") (pin "5") (pinfunction "IO34_5") (pintype "bidirectional"))
      (node (ref "R13") (pin "2") (pintype "passive"))
      (node (ref "T2") (pin "1") (pinfunction "C_1") (pintype "passive"))
    )
    (net (code "26") (name "Net-(IC1A-B)") (class "Default")
      (node (ref "IC1") (pin "2") (pinfunction "B_2") (pintype "input"))
      (node (ref "MCU ESP32") (pin "10") (pinfunction "IO26_10") (pintype "bidirectional"))
    )
    (net (code "27") (name "Net-(IC1B-C)") (class "Default")
      (node (ref "C14") (pin "1") (pinfunction "1_1") (pintype "passive"))
      (node (ref "IC1") (pin "5") (pinfunction "C_5") (pintype "input"))
      (node (ref "R2") (pin "2") (pintype "passive"))
      (node (ref "R21") (pin "2") (pintype "passive"))
    )
    (net (code "28") (name "Net-(IC1B-D)") (class "Default")
      (node (ref "IC1") (pin "6") (pinfunction "D_6") (pintype "input"))
      (node (ref "MCU ESP32") (pin "11") (pinfunction "IO27_11") (pintype "bidirectional"))
    )
    (net (code "29") (name "Net-(IC1B-K)") (class "Default")
      (node (ref "IC1") (pin "4") (pinfunction "K_4") (pintype "output"))
      (node (ref "IC1") (pin "8") (pinfunction "E_8") (pintype "input"))
      (node (ref "IC1") (pin "9") (pinfunction "F_9") (pintype "input"))
    )
    (net (code "30") (name "Net-(IC1C-L)") (class "Default")
      (node (ref "IC1") (pin "10") (pinfunction "L_10") (pintype "output"))
      (node (ref "R7") (pin "2") (pintype "passive"))
    )
    (net (code "31") (name "Net-(IC3-SX)") (class "Default")
      (node (ref "IC3") (pin "3") (pinfunction "SX_3") (pintype "bidirectional"))
      (node (ref "IC4") (pin "14") (pinfunction "SCL_14") (pintype "input"))
      (node (ref "R8") (pin "1") (pintype "passive"))
      (node (ref "T5") (pin "3") (pinfunction "D_3") (pintype "passive"))
    )
    (net (code "32") (name "Net-(IC3-SY)") (class "Default")
      (node (ref "IC3") (pin "6") (pinfunction "SY_6") (pintype "bidirectional"))
      (node (ref "IC4") (pin "15") (pinfunction "SDA_15") (pintype "bidirectional"))
      (node (ref "R9") (pin "1") (pintype "passive"))
      (node (ref "T4") (pin "3") (pinfunction "D_3") (pintype "passive"))
    )
    (net (code "33") (name "Net-(IC4-P0)") (class "Default")
      (node (ref "IC4") (pin "4") (pinfunction "P0_4") (pintype "bidirectional"))
      (node (ref "lcd") (pin "5") (pinfunction "R/W_5") (pintype "input"))
    )
    (net (code "34") (name "Net-(IC4-P1)") (class "Default")
      (node (ref "IC4") (pin "5") (pinfunction "P1_5") (pintype "bidirectional"))
      (node (ref "lcd") (pin "6") (pinfunction "E_6") (pintype "input"))
    )
    (net (code "35") (name "Net-(IC4-P2)") (class "Default")
      (node (ref "IC4") (pin "6") (pinfunction "P2_6") (pintype "bidirectional"))
      (node (ref "lcd") (pin "7") (pinfunction "DB0_7") (pintype "input"))
    )
    (net (code "36") (name "Net-(IC4-P4)") (class "Default")
      (node (ref "IC4") (pin "9") (pinfunction "P4_9") (pintype "bidirectional"))
      (node (ref "lcd") (pin "11") (pinfunction "DB4_11") (pintype "input"))
    )
    (net (code "37") (name "Net-(IC4-P5)") (class "Default")
      (node (ref "IC4") (pin "10") (pinfunction "P5_10") (pintype "bidirectional"))
      (node (ref "lcd") (pin "12") (pinfunction "DB5_12") (pintype "input"))
    )
    (net (code "38") (name "Net-(IC4-P6)") (class "Default")
      (node (ref "IC4") (pin "11") (pinfunction "P6_11") (pintype "bidirectional"))
      (node (ref "lcd") (pin "13") (pinfunction "DB6_13") (pintype "input"))
    )
    (net (code "39") (name "Net-(IC4-P7)") (class "Default")
      (node (ref "IC4") (pin "12") (pinfunction "P7_12") (pintype "bidirectional"))
      (node (ref "lcd") (pin "14") (pinfunction "DB7_14") (pintype "input"))
    )
    (net (code "40") (name "Net-(IC5-CONTROL_VOLTAGE)") (class "Default")
      (node (ref "IC5") (pin "5") (pinfunction "CONTROL_VOLTAGE_5") (pintype "passive"))
      (node (ref "R18") (pin "1") (pintype "passive"))
      (node (ref "T3") (pin "1") (pinfunction "C_1") (pintype "passive"))
    )
    (net (code "41") (name "Net-(IC5-DISCHARGE)") (class "Default")
      (node (ref "IC5") (pin "7") (pinfunction "DISCHARGE_7") (pintype "passive"))
      (node (ref "R19") (pin "2") (pintype "passive"))
      (node (ref "R6") (pin "1") (pintype "passive"))
    )
    (net (code "42") (name "Net-(IC5-OUTPUT)") (class "Default")
      (node (ref "IC5") (pin "3") (pinfunction "OUTPUT_3") (pintype "passive"))
      (node (ref "R1") (pin "2") (pintype "passive"))
    )
    (net (code "43") (name "Net-(IC5-THRESHOLD)") (class "Default")
      (node (ref "C2") (pin "2") (pinfunction "2_2") (pintype "passive"))
      (node (ref "IC5") (pin "2") (pinfunction "~{TRIGGER}_2") (pintype "passive"))
      (node (ref "IC5") (pin "6") (pinfunction "THRESHOLD_6") (pintype "passive"))
      (node (ref "R19") (pin "1") (pintype "passive"))
    )
    (net (code "44") (name "Net-(K2-Pad1)") (class "Default")
      (node (ref "K2") (pin "1") (pinfunction "1_1") (pintype "passive"))
      (node (ref "R25") (pin "2") (pintype "passive"))
    )
    (net (code "45") (name "Net-(LED1-A)") (class "Default")
      (node (ref "LED1") (pin "1") (pinfunction "A_1") (pintype "passive"))
      (node (ref "R3") (pin "2") (pintype "passive"))
    )
    (net (code "46") (name "Net-(LED1-K)") (class "Default")
      (node (ref "BZ1") (pin "2") (pinfunction "2_2") (pintype "passive"))
      (node (ref "LED1") (pin "2") (pinfunction "K_2") (pintype "passive"))
      (node (ref "T1") (pin "1") (pinfunction "C_1") (pintype "passive"))
    )
    (net (code "47") (name "Net-(MCU ESP32-IO15)") (class "Default")
      (node (ref "MCU ESP32") (pin "35") (pinfunction "IO15_35") (pintype "bidirectional"))
      (node (ref "R16") (pin "1") (pintype "passive"))
      (node (ref "SW3") (pin "3") (pinfunction "3_3") (pintype "passive"))
      (node (ref "SW3") (pin "4") (pinfunction "4_4") (pintype "passive"))
    )
    (net (code "48") (name "Net-(MCU ESP32-IO16)") (class "Default")
      (node (ref "MCU ESP32") (pin "31") (pinfunction "IO16_31") (pintype "bidirectional"))
      (node (ref "R15") (pin "1") (pintype "passive"))
      (node (ref "SW2") (pin "3") (pinfunction "3_3") (pintype "passive"))
      (node (ref "SW2") (pin "4") (pinfunction "4_4") (pintype "passive"))
    )
    (net (code "49") (name "Net-(MCU ESP32-IO17)") (class "Default")
      (node (ref "MCU ESP32") (pin "30") (pinfunction "IO17_30") (pintype "bidirectional"))
      (node (ref "R14") (pin "1") (pintype "passive"))
      (node (ref "SW1") (pin "3") (pinfunction "3_3") (pintype "passive"))
      (node (ref "SW1") (pin "4") (pinfunction "4_4") (pintype "passive"))
    )
    (net (code "50") (name "Net-(MCU ESP32-IO21)") (class "Default")
      (node (ref "MCU ESP32") (pin "25") (pinfunction "IO21_25") (pintype "bidirectional"))
      (node (ref "R10") (pin "1") (pintype "passive"))
      (node (ref "T4") (pin "1") (pinfunction "S_1") (pintype "passive"))
    )
    (net (code "51") (name "Net-(MCU ESP32-IO22)") (class "Default")
      (node (ref "MCU ESP32") (pin "22") (pinfunction "IO22_22") (pintype "bidirectional"))
      (node (ref "R11") (pin "1") (pintype "passive"))
      (node (ref "T5") (pin "1") (pinfunction "S_1") (pintype "passive"))
    )
    (net (code "52") (name "Net-(R22-Pad2)") (class "Default")
      (node (ref "R22") (pin "2") (pintype "passive"))
      (node (ref "R24") (pin "1") (pintype "passive"))
    )
    (net (code "53") (name "Net-(T1-B)") (class "Default")
      (node (ref "R7") (pin "1") (pintype "passive"))
      (node (ref "T1") (pin "2") (pinfunction "B_2") (pintype "passive"))
    )
    (net (code "54") (name "Net-(T2-B)") (class "Default")
      (node (ref "R17") (pin "1") (pintype "passive"))
      (node (ref "T2") (pin "2") (pinfunction "B_2") (pintype "passive"))
    )
    (net (code "55") (name "Net-(T2-E)") (class "Default")
      (node (ref "R20") (pin "1") (pintype "passive"))
      (node (ref "T2") (pin "3") (pinfunction "E_3") (pintype "passive"))
    )
    (net (code "56") (name "Net-(T3-B)") (class "Default")
      (node (ref "R12") (pin "2") (pintype "passive"))
      (node (ref "R22") (pin "1") (pintype "passive"))
      (node (ref "T3") (pin "2") (pinfunction "B_2") (pintype "passive"))
    )
    (net (code "57") (name "Net-(T6-G)") (class "Default")
      (node (ref "R1") (pin "1") (pintype "passive"))
      (node (ref "T6") (pin "1") (pinfunction "G_1") (pintype "passive"))
    )
    (net (code "58") (name "Net-(VR1-WIPER)") (class "Default")
      (node (ref "VR1") (pin "2") (pinfunction "WIPER_2") (pintype "passive"))
      (node (ref "lcd") (pin "3") (pinfunction "V0_3") (pintype "input"))
    )
    (net (code "59") (name "Net-(VR2-CCW)") (class "Default")
      (node (ref "R12") (pin "1") (pintype "passive"))
      (node (ref "VR2") (pin "1") (pinfunction "CCW_1") (pintype "passive"))
    )
    (net (code "60") (name "Ub") (class "Default")
      (node (ref "C21") (pin "2") (pintype "passive"))
      (node (ref "D6") (pin "1") (pinfunction "K_1") (pintype "passive"))
      (node (ref "IC2") (pin "1") (pinfunction "VIN_1") (pintype "passive"))
      (node (ref "J1") (pin "7") (pinfunction "7_7") (pintype "passive"))
      (node (ref "J2") (pin "7") (pinfunction "7_7") (pintype "passive"))
      (node (ref "J3") (pin "7") (pinfunction "7_7") (pintype "passive"))
    )
    (net (code "61") (name "unconnected-(IC1D-G-Pad12)") (class "Default")
      (node (ref "IC1") (pin "12") (pinfunction "G_12") (pintype "input+no_connect"))
    )
    (net (code "62") (name "unconnected-(IC1D-H-Pad13)") (class "Default")
      (node (ref "IC1") (pin "13") (pinfunction "H_13") (pintype "input+no_connect"))
    )
    (net (code "63") (name "unconnected-(IC1D-M-Pad11)") (class "Default")
      (node (ref "IC1") (pin "11") (pinfunction "M_11") (pintype "output+no_connect"))
    )
    (net (code "64") (name "unconnected-(IC3-NC-Pad1)") (class "Default")
      (node (ref "IC3") (pin "1") (pinfunction "NC_1") (pintype "passive"))
    )
    (net (code "65") (name "unconnected-(IC3-NC-Pad5)") (class "Default")
      (node (ref "IC3") (pin "5") (pinfunction "NC_5") (pintype "passive"))
    )
    (net (code "66") (name "unconnected-(IC4-P3-Pad7)") (class "Default")
      (node (ref "IC4") (pin "7") (pinfunction "P3_7") (pintype "bidirectional"))
    )
    (net (code "67") (name "unconnected-(IC4-~{INT}-Pad13)") (class "Default")
      (node (ref "IC4") (pin "13") (pinfunction "~{INT}_13") (pintype "open_collector"))
    )
    (net (code "68") (name "unconnected-(MCU ESP32-CLK-Pad38)") (class "Default")
      (node (ref "MCU ESP32") (pin "38") (pinfunction "CLK_38") (pintype "input+no_connect"))
    )
    (net (code "69") (name "unconnected-(MCU ESP32-CMD-Pad18)") (class "Default")
      (node (ref "MCU ESP32") (pin "18") (pinfunction "CMD_18") (pintype "bidirectional"))
    )
    (net (code "70") (name "unconnected-(MCU ESP32-EN-Pad2)") (class "Default")
      (node (ref "MCU ESP32") (pin "2") (pinfunction "EN_2") (pintype "input+no_connect"))
    )
    (net (code "71") (name "unconnected-(MCU ESP32-IO0-Pad33)") (class "Default")
      (node (ref "MCU ESP32") (pin "33") (pinfunction "IO0_33") (pintype "bidirectional"))
    )
    (net (code "72") (name "unconnected-(MCU ESP32-IO2-Pad34)") (class "Default")
      (node (ref "MCU ESP32") (pin "34") (pinfunction "IO2_34") (pintype "bidirectional"))
    )
    (net (code "73") (name "unconnected-(MCU ESP32-IO4-Pad32)") (class "Default")
      (node (ref "MCU ESP32") (pin "32") (pinfunction "IO4_32") (pintype "bidirectional"))
    )
    (net (code "74") (name "unconnected-(MCU ESP32-IO5-Pad29)") (class "Default")
      (node (ref "MCU ESP32") (pin "29") (pinfunction "IO5_29") (pintype "bidirectional"))
    )
    (net (code "75") (name "unconnected-(MCU ESP32-IO12-Pad13)") (class "Default")
      (node (ref "MCU ESP32") (pin "13") (pinfunction "IO12_13") (pintype "bidirectional"))
    )
    (net (code "76") (name "unconnected-(MCU ESP32-IO13-Pad15)") (class "Default")
      (node (ref "MCU ESP32") (pin "15") (pinfunction "IO13_15") (pintype "bidirectional"))
    )
    (net (code "77") (name "unconnected-(MCU ESP32-IO14-Pad12)") (class "Default")
      (node (ref "MCU ESP32") (pin "12") (pinfunction "IO14_12") (pintype "bidirectional"))
    )
    (net (code "78") (name "unconnected-(MCU ESP32-IO18-Pad28)") (class "Default")
      (node (ref "MCU ESP32") (pin "28") (pinfunction "IO18_28") (pintype "bidirectional"))
    )
    (net (code "79") (name "unconnected-(MCU ESP32-IO19-Pad27)") (class "Default")
      (node (ref "MCU ESP32") (pin "27") (pinfunction "IO19_27") (pintype "bidirectional"))
    )
    (net (code "80") (name "unconnected-(MCU ESP32-IO23-Pad21)") (class "Default")
      (node (ref "MCU ESP32") (pin "21") (pinfunction "IO23_21") (pintype "bidirectional"))
    )
    (net (code "81") (name "unconnected-(MCU ESP32-IO25-Pad9)") (class "Default")
      (node (ref "MCU ESP32") (pin "9") (pinfunction "IO25_9") (pintype "bidirectional"))
    )
    (net (code "82") (name "unconnected-(MCU ESP32-IO32-Pad7)") (class "Default")
      (node (ref "MCU ESP32") (pin "7") (pinfunction "IO32_7") (pintype "bidirectional"))
    )
    (net (code "83") (name "unconnected-(MCU ESP32-IO33-Pad8)") (class "Default")
      (node (ref "MCU ESP32") (pin "8") (pinfunction "IO33_8") (pintype "bidirectional"))
    )
    (net (code "84") (name "unconnected-(MCU ESP32-IO35-Pad6)") (class "Default")
      (node (ref "MCU ESP32") (pin "6") (pinfunction "IO35_6") (pintype "bidirectional"))
    )
    (net (code "85") (name "unconnected-(MCU ESP32-RXD0-Pad24)") (class "Default")
      (node (ref "MCU ESP32") (pin "24") (pinfunction "RXD0_24") (pintype "input+no_connect"))
    )
    (net (code "86") (name "unconnected-(MCU ESP32-SD0-Pad37)") (class "Default")
      (node (ref "MCU ESP32") (pin "37") (pinfunction "SD0_37") (pintype "bidirectional"))
    )
    (net (code "87") (name "unconnected-(MCU ESP32-SD1-Pad36)") (class "Default")
      (node (ref "MCU ESP32") (pin "36") (pinfunction "SD1_36") (pintype "bidirectional"))
    )
    (net (code "88") (name "unconnected-(MCU ESP32-SD2-Pad16)") (class "Default")
      (node (ref "MCU ESP32") (pin "16") (pinfunction "SD2_16") (pintype "bidirectional"))
    )
    (net (code "89") (name "unconnected-(MCU ESP32-SD3-Pad17)") (class "Default")
      (node (ref "MCU ESP32") (pin "17") (pinfunction "SD3_17") (pintype "bidirectional"))
    )
    (net (code "90") (name "unconnected-(MCU ESP32-SENSOR_VN-Pad4)") (class "Default")
      (node (ref "MCU ESP32") (pin "4") (pinfunction "SENSOR_VN_4") (pintype "input+no_connect"))
    )
    (net (code "91") (name "unconnected-(MCU ESP32-SENSOR_VP-Pad3)") (class "Default")
      (node (ref "MCU ESP32") (pin "3") (pinfunction "SENSOR_VP_3") (pintype "input+no_connect"))
    )
    (net (code "92") (name "unconnected-(MCU ESP32-TXD0-Pad23)") (class "Default")
      (node (ref "MCU ESP32") (pin "23") (pinfunction "TXD0_23") (pintype "output"))
    )
    (net (code "93") (name "unconnected-(lcd-DB1-Pad8)") (class "Default")
      (node (ref "lcd") (pin "8") (pinfunction "DB1_8") (pintype "input+no_connect"))
    )
    (net (code "94") (name "unconnected-(lcd-DB2-Pad9)") (class "Default")
      (node (ref "lcd") (pin "9") (pinfunction "DB2_9") (pintype "input+no_connect"))
    )
    (net (code "95") (name "unconnected-(lcd-DB3-Pad10)") (class "Default")
      (node (ref "lcd") (pin "10") (pinfunction "DB3_10") (pintype "input+no_connect"))
    )
  )
)
